# MSP430F149.net
KiCad netlist of a schematic drawn in Altium Designer
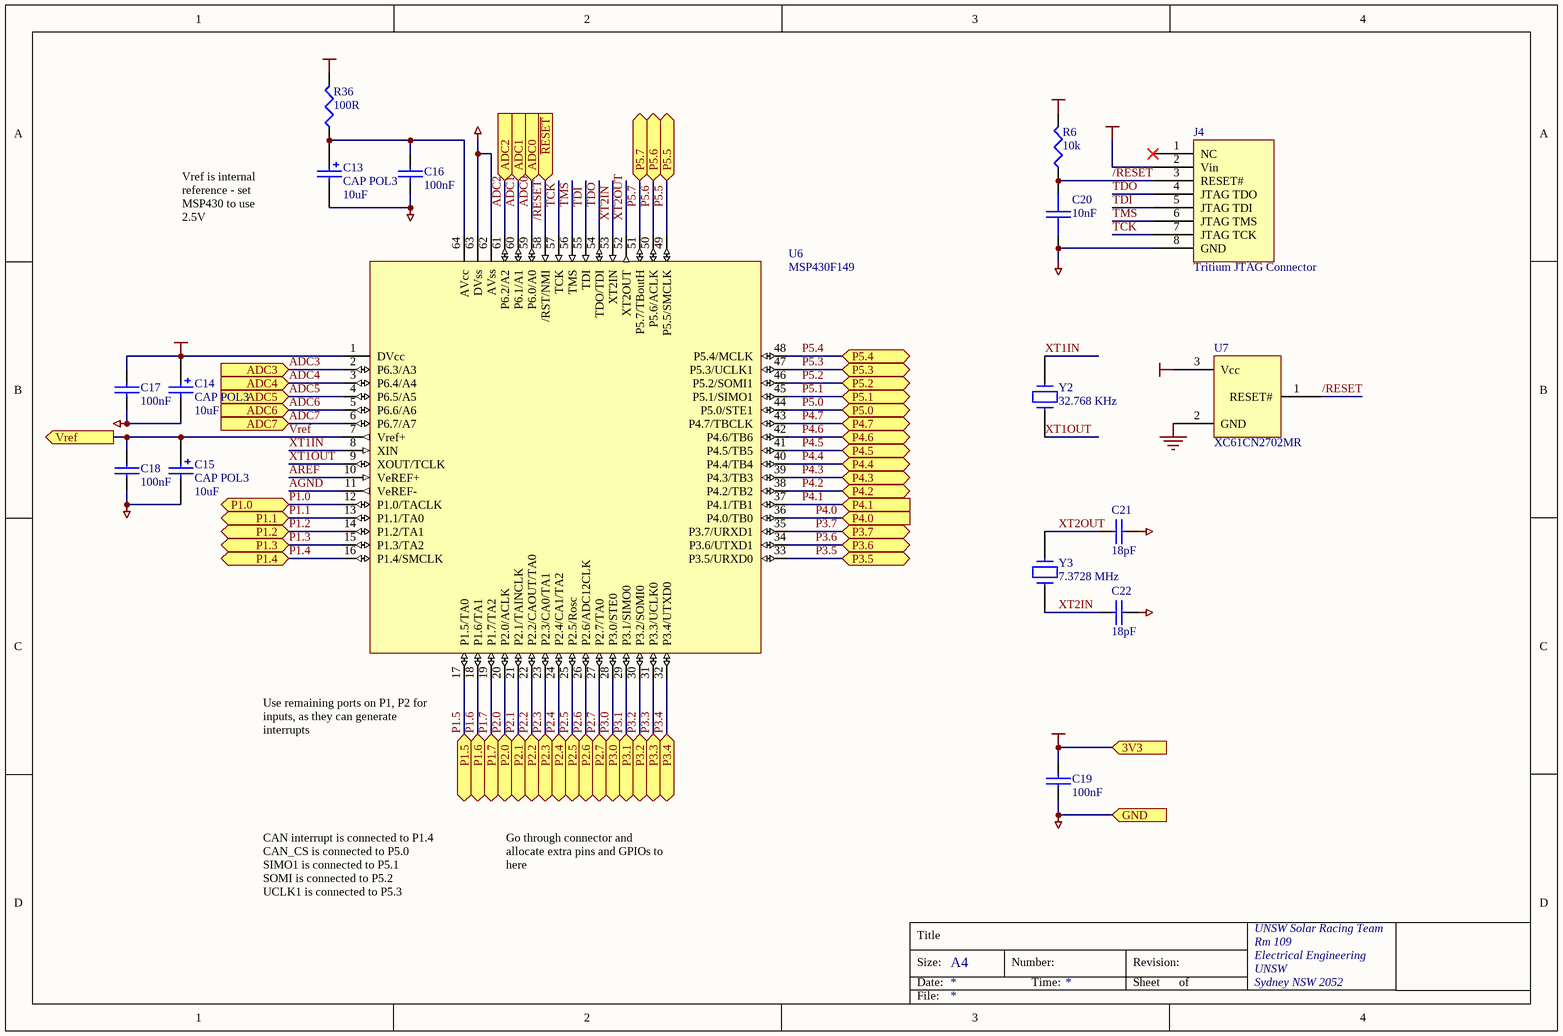
[diagram p0: MSP430F149.SCHDOC]

(export (version "E")
  (design (tool "Eeschema 10.0.6"))
  (components
    (comp (ref "C13")
      (value "CAP POL3")
      (footprint "MCCT-CASEA")
      (description "Polarized Capacitor (Surface Mount)")
      (fields
        (field (name "MANUFACTURER") "Generic Components")
        (field (name "ALTIUM_VALUE") "10uF")
        (field (name "PUBLISHER") "Altium Limited")
      )
      (libsource (lib "RCLDQ") (part "CAP POL3"))
    )
    (comp (ref "C14")
      (value "CAP POL3")
      (footprint "MCCT-CASEA")
      (description "Polarized Capacitor (Surface Mount)")
      (fields
        (field (name "MANUFACTURER") "Generic Components")
        (field (name "ALTIUM_VALUE") "10uF")
        (field (name "PUBLISHER") "Altium Limited")
      )
      (libsource (lib "RCLDQ") (part "CAP POL3"))
    )
    (comp (ref "C15")
      (value "CAP POL3")
      (footprint "MCCT-CASEA")
      (description "Polarized Capacitor (Surface Mount)")
      (fields
        (field (name "MANUFACTURER") "Generic Components")
        (field (name "ALTIUM_VALUE") "10uF")
        (field (name "PUBLISHER") "Altium Limited")
      )
      (libsource (lib "RCLDQ") (part "CAP POL3"))
    )
    (comp (ref "C16")
      (value "100nF")
      (footprint "0603")
      (description "Capacitor")
      (libsource (lib "*") (part "CAP"))
    )
    (comp (ref "C17")
      (value "100nF")
      (footprint "0603")
      (description "Capacitor")
      (libsource (lib "*") (part "CAP"))
    )
    (comp (ref "C18")
      (value "100nF")
      (footprint "0603")
      (description "Capacitor")
      (libsource (lib "*") (part "CAP"))
    )
    (comp (ref "C19")
      (value "100nF")
      (footprint "0603")
      (description "Capacitor")
      (libsource (lib "*") (part "CAP"))
    )
    (comp (ref "C20")
      (value "10nF")
      (footprint "0603")
      (description "Capacitor")
      (libsource (lib "SunswiftLib20030312RR") (part "CAP"))
    )
    (comp (ref "C21")
      (value "18pF")
      (footprint "0603")
      (description "Capacitor")
      (libsource (lib "*") (part "CAP"))
    )
    (comp (ref "C22")
      (value "18pF")
      (footprint "0603")
      (description "Capacitor")
      (libsource (lib "*") (part "CAP"))
    )
    (comp (ref "J4")
      (value "Tritium JTAG Connector")
      (footprint "HDR2X5")
      (description "Tritium JTAG interface for MSP430")
      (libsource (lib "SunswiftLib20030312RR") (part "430F_JTAG_TRITIUM"))
    )
    (comp (ref "R6")
      (value "10k")
      (footprint "0603")
      (description "Resistor")
      (libsource (lib "SunswiftLib20030312RR") (part "RES1"))
    )
    (comp (ref "R36")
      (value "100R")
      (footprint "0603")
      (description "Resistor")
      (libsource (lib "SunswiftLib20030312RR") (part "RES1"))
    )
    (comp (ref "U6")
      (value "MSP430F149")
      (footprint "QFP64")
      (libsource (lib "SunswiftLib20030312RR") (part "MSP430F14X"))
    )
    (comp (ref "U7")
      (value "XC61CN2702MR")
      (footprint "SOT23-3")
      (description "SOT23 reset generator")
      (libsource (lib "*") (part "XC61F"))
    )
    (comp (ref "Y2")
      (value "32.768 KHz")
      (footprint "WATCHA")
      (description "Crystal")
      (libsource (lib "*") (part "CRYSTAL"))
    )
    (comp (ref "Y3")
      (value "7.3728 MHz")
      (footprint "HC49/4H")
      (description "Crystal")
      (libsource (lib "*") (part "CRYSTAL"))
    )
  )
  (nets
    (net (code "1") (name "/ADC0") (class "Default")
      (node (ref "U6") (pin "59") (pinfunction "P6.0/A0_59") (pintype "bidirectional"))
    )
    (net (code "2") (name "/ADC1") (class "Default")
      (node (ref "U6") (pin "60") (pinfunction "P6.1/A1_60") (pintype "bidirectional"))
    )
    (net (code "3") (name "/ADC2") (class "Default")
      (node (ref "U6") (pin "61") (pinfunction "P6.2/A2_61") (pintype "bidirectional"))
    )
    (net (code "4") (name "/ADC3") (class "Default")
      (node (ref "U6") (pin "2") (pinfunction "P6.3/A3_2") (pintype "bidirectional"))
    )
    (net (code "5") (name "/ADC4") (class "Default")
      (node (ref "U6") (pin "3") (pinfunction "P6.4/A4_3") (pintype "bidirectional"))
    )
    (net (code "6") (name "/ADC5") (class "Default")
      (node (ref "U6") (pin "4") (pinfunction "P6.5/A5_4") (pintype "bidirectional"))
    )
    (net (code "7") (name "/ADC6") (class "Default")
      (node (ref "U6") (pin "5") (pinfunction "P6.6/A6_5") (pintype "bidirectional"))
    )
    (net (code "8") (name "/ADC7") (class "Default")
      (node (ref "U6") (pin "6") (pinfunction "P6.7/A7_6") (pintype "bidirectional"))
    )
    (net (code "9") (name "/AGND") (class "Default")
      (node (ref "U6") (pin "11") (pinfunction "VeREF-_11") (pintype "output"))
    )
    (net (code "10") (name "/AREF") (class "Default")
      (node (ref "U6") (pin "10") (pinfunction "VeREF+_10") (pintype "input"))
    )
    (net (code "11") (name "/P1.0") (class "Default")
      (node (ref "U6") (pin "12") (pinfunction "P1.0/TACLK_12") (pintype "bidirectional"))
    )
    (net (code "12") (name "/P1.1") (class "Default")
      (node (ref "U6") (pin "13") (pinfunction "P1.1/TA0_13") (pintype "bidirectional"))
    )
    (net (code "13") (name "/P1.2") (class "Default")
      (node (ref "U6") (pin "14") (pinfunction "P1.2/TA1_14") (pintype "bidirectional"))
    )
    (net (code "14") (name "/P1.3") (class "Default")
      (node (ref "U6") (pin "15") (pinfunction "P1.3/TA2_15") (pintype "bidirectional"))
    )
    (net (code "15") (name "/P1.4") (class "Default")
      (node (ref "U6") (pin "16") (pinfunction "P1.4/SMCLK_16") (pintype "bidirectional"))
    )
    (net (code "16") (name "/P1.5") (class "Default")
      (node (ref "U6") (pin "17") (pinfunction "P1.5/TA0_17") (pintype "bidirectional"))
    )
    (net (code "17") (name "/P1.6") (class "Default")
      (node (ref "U6") (pin "18") (pinfunction "P1.6/TA1_18") (pintype "bidirectional"))
    )
    (net (code "18") (name "/P1.7") (class "Default")
      (node (ref "U6") (pin "19") (pinfunction "P1.7/TA2_19") (pintype "bidirectional"))
    )
    (net (code "19") (name "/P2.0") (class "Default")
      (node (ref "U6") (pin "20") (pinfunction "P2.0/ACLK_20") (pintype "bidirectional"))
    )
    (net (code "20") (name "/P2.1") (class "Default")
      (node (ref "U6") (pin "21") (pinfunction "P2.1/TAINCLK_21") (pintype "bidirectional"))
    )
    (net (code "21") (name "/P2.2") (class "Default")
      (node (ref "U6") (pin "22") (pinfunction "P2.2/CAOUT/TA0_22") (pintype "bidirectional"))
    )
    (net (code "22") (name "/P2.3") (class "Default")
      (node (ref "U6") (pin "23") (pinfunction "P2.3/CA0/TA1_23") (pintype "bidirectional"))
    )
    (net (code "23") (name "/P2.4") (class "Default")
      (node (ref "U6") (pin "24") (pinfunction "P2.4/CA1/TA2_24") (pintype "bidirectional"))
    )
    (net (code "24") (name "/P2.5") (class "Default")
      (node (ref "U6") (pin "25") (pinfunction "P2.5/Rosc_25") (pintype "bidirectional"))
    )
    (net (code "25") (name "/P2.6") (class "Default")
      (node (ref "U6") (pin "26") (pinfunction "P2.6/ADC12CLK_26") (pintype "bidirectional"))
    )
    (net (code "26") (name "/P2.7") (class "Default")
      (node (ref "U6") (pin "27") (pinfunction "P2.7/TA0_27") (pintype "bidirectional"))
    )
    (net (code "27") (name "/P3.0") (class "Default")
      (node (ref "U6") (pin "28") (pinfunction "P3.0/STE0_28") (pintype "bidirectional"))
    )
    (net (code "28") (name "/P3.1") (class "Default")
      (node (ref "U6") (pin "29") (pinfunction "P3.1/SIMO0_29") (pintype "bidirectional"))
    )
    (net (code "29") (name "/P3.2") (class "Default")
      (node (ref "U6") (pin "30") (pinfunction "P3.2/SOMI0_30") (pintype "bidirectional"))
    )
    (net (code "30") (name "/P3.3") (class "Default")
      (node (ref "U6") (pin "31") (pinfunction "P3.3/UCLK0_31") (pintype "bidirectional"))
    )
    (net (code "31") (name "/P3.4") (class "Default")
      (node (ref "U6") (pin "32") (pinfunction "P3.4/UTXD0_32") (pintype "bidirectional"))
    )
    (net (code "32") (name "/P3.5") (class "Default")
      (node (ref "U6") (pin "33") (pinfunction "P3.5/URXD0_33") (pintype "bidirectional"))
    )
    (net (code "33") (name "/P3.6") (class "Default")
      (node (ref "U6") (pin "34") (pinfunction "P3.6/UTXD1_34") (pintype "bidirectional"))
    )
    (net (code "34") (name "/P3.7") (class "Default")
      (node (ref "U6") (pin "35") (pinfunction "P3.7/URXD1_35") (pintype "bidirectional"))
    )
    (net (code "35") (name "/P4.0") (class "Default")
      (node (ref "U6") (pin "36") (pinfunction "P4.0/TB0_36") (pintype "bidirectional"))
    )
    (net (code "36") (name "/P4.1") (class "Default")
      (node (ref "U6") (pin "37") (pinfunction "P4.1/TB1_37") (pintype "bidirectional"))
    )
    (net (code "37") (name "/P4.2") (class "Default")
      (node (ref "U6") (pin "38") (pinfunction "P4.2/TB2_38") (pintype "bidirectional"))
    )
    (net (code "38") (name "/P4.3") (class "Default")
      (node (ref "U6") (pin "39") (pinfunction "P4.3/TB3_39") (pintype "bidirectional"))
    )
    (net (code "39") (name "/P4.4") (class "Default")
      (node (ref "U6") (pin "40") (pinfunction "P4.4/TB4_40") (pintype "bidirectional"))
    )
    (net (code "40") (name "/P4.5") (class "Default")
      (node (ref "U6") (pin "41") (pinfunction "P4.5/TB5_41") (pintype "bidirectional"))
    )
    (net (code "41") (name "/P4.6") (class "Default")
      (node (ref "U6") (pin "42") (pinfunction "P4.6/TB6_42") (pintype "bidirectional"))
    )
    (net (code "42") (name "/P4.7") (class "Default")
      (node (ref "U6") (pin "43") (pinfunction "P4.7/TBCLK_43") (pintype "bidirectional"))
    )
    (net (code "43") (name "/P5.0") (class "Default")
      (node (ref "U6") (pin "44") (pinfunction "P5.0/STE1_44") (pintype "bidirectional"))
    )
    (net (code "44") (name "/P5.1") (class "Default")
      (node (ref "U6") (pin "45") (pinfunction "P5.1/SIMO1_45") (pintype "bidirectional"))
    )
    (net (code "45") (name "/P5.2") (class "Default")
      (node (ref "U6") (pin "46") (pinfunction "P5.2/SOMI1_46") (pintype "bidirectional"))
    )
    (net (code "46") (name "/P5.3") (class "Default")
      (node (ref "U6") (pin "47") (pinfunction "P5.3/UCLK1_47") (pintype "bidirectional"))
    )
    (net (code "47") (name "/P5.4") (class "Default")
      (node (ref "U6") (pin "48") (pinfunction "P5.4/MCLK_48") (pintype "bidirectional"))
    )
    (net (code "48") (name "/P5.5") (class "Default")
      (node (ref "U6") (pin "49") (pinfunction "P5.5/SMCLK_49") (pintype "bidirectional"))
    )
    (net (code "49") (name "/P5.6") (class "Default")
      (node (ref "U6") (pin "50") (pinfunction "P5.6/ACLK_50") (pintype "bidirectional"))
    )
    (net (code "50") (name "/P5.7") (class "Default")
      (node (ref "U6") (pin "51") (pinfunction "P5.7/TBoutH_51") (pintype "bidirectional"))
    )
    (net (code "51") (name "/TCK") (class "Default")
      (node (ref "J4") (pin "7") (pinfunction "JTAG_TCK_7") (pintype "passive"))
      (node (ref "U6") (pin "57") (pinfunction "TCK_57") (pintype "input"))
    )
    (net (code "52") (name "/TDI") (class "Default")
      (node (ref "J4") (pin "5") (pinfunction "JTAG_TDI_5") (pintype "passive"))
      (node (ref "U6") (pin "55") (pinfunction "TDI_55") (pintype "input"))
    )
    (net (code "53") (name "/TDO") (class "Default")
      (node (ref "J4") (pin "4") (pinfunction "JTAG_TDO_4") (pintype "passive"))
      (node (ref "U6") (pin "54") (pinfunction "TDO/TDI_54") (pintype "bidirectional"))
    )
    (net (code "54") (name "/TMS") (class "Default")
      (node (ref "J4") (pin "6") (pinfunction "JTAG_TMS_6") (pintype "passive"))
      (node (ref "U6") (pin "56") (pinfunction "TMS_56") (pintype "input"))
    )
    (net (code "55") (name "/Vref") (class "Default")
      (node (ref "C15") (pin "1") (pinfunction "1_1") (pintype "passive"))
      (node (ref "C18") (pin "1") (pinfunction "1_1") (pintype "passive"))
      (node (ref "U6") (pin "7") (pinfunction "Vref+_7") (pintype "output"))
    )
    (net (code "56") (name "/XT1IN") (class "Default")
      (node (ref "U6") (pin "8") (pinfunction "XIN_8") (pintype "input"))
      (node (ref "Y2") (pin "1") (pinfunction "1_1") (pintype "passive"))
    )
    (net (code "57") (name "/XT1OUT") (class "Default")
      (node (ref "U6") (pin "9") (pinfunction "XOUT/TCLK_9") (pintype "bidirectional"))
      (node (ref "Y2") (pin "2") (pinfunction "2_2") (pintype "passive"))
    )
    (net (code "58") (name "/XT2IN") (class "Default")
      (node (ref "C22") (pin "1") (pinfunction "1_1") (pintype "passive"))
      (node (ref "U6") (pin "53") (pinfunction "XT2IN_53") (pintype "input"))
      (node (ref "Y3") (pin "1") (pinfunction "1_1") (pintype "passive"))
    )
    (net (code "59") (name "/XT2OUT") (class "Default")
      (node (ref "C21") (pin "1") (pinfunction "1_1") (pintype "passive"))
      (node (ref "U6") (pin "52") (pinfunction "XT2OUT_52") (pintype "output"))
      (node (ref "Y3") (pin "2") (pinfunction "2_2") (pintype "passive"))
    )
    (net (code "60") (name "/{slash}RESET") (class "Default")
      (node (ref "C20") (pin "1") (pinfunction "1_1") (pintype "passive"))
      (node (ref "J4") (pin "3") (pinfunction "RESET#_3") (pintype "passive"))
      (node (ref "R6") (pin "1") (pinfunction "1_1") (pintype "passive"))
      (node (ref "U6") (pin "58") (pinfunction "/RST/NMI_58") (pintype "input"))
      (node (ref "U7") (pin "1") (pinfunction "RESET#_1") (pintype "passive"))
    )
    (net (code "61") (name "3V3") (class "Default")
      (node (ref "C14") (pin "1") (pinfunction "1_1") (pintype "passive"))
      (node (ref "C17") (pin "1") (pinfunction "1_1") (pintype "passive"))
      (node (ref "C19") (pin "1") (pinfunction "1_1") (pintype "passive"))
      (node (ref "J4") (pin "2") (pinfunction "Vin_2") (pintype "passive"))
      (node (ref "R36") (pin "2") (pinfunction "2_2") (pintype "passive"))
      (node (ref "R6") (pin "2") (pinfunction "2_2") (pintype "passive"))
      (node (ref "U6") (pin "1") (pinfunction "DVcc_1") (pintype "power_in"))
      (node (ref "U7") (pin "3") (pinfunction "Vcc_3") (pintype "passive"))
    )
    (net (code "62") (name "GND") (class "Default")
      (node (ref "C13") (pin "2") (pinfunction "2_2") (pintype "passive"))
      (node (ref "C14") (pin "2") (pinfunction "2_2") (pintype "passive"))
      (node (ref "C15") (pin "2") (pinfunction "2_2") (pintype "passive"))
      (node (ref "C16") (pin "2") (pinfunction "2_2") (pintype "passive"))
      (node (ref "C17") (pin "2") (pinfunction "2_2") (pintype "passive"))
      (node (ref "C18") (pin "2") (pinfunction "2_2") (pintype "passive"))
      (node (ref "C19") (pin "2") (pinfunction "2_2") (pintype "passive"))
      (node (ref "C20") (pin "2") (pinfunction "2_2") (pintype "passive"))
      (node (ref "C21") (pin "2") (pinfunction "2_2") (pintype "passive"))
      (node (ref "C22") (pin "2") (pinfunction "2_2") (pintype "passive"))
      (node (ref "J4") (pin "8") (pinfunction "GND_8") (pintype "passive"))
      (node (ref "U6") (pin "62") (pinfunction "AVss_62") (pintype "power_in"))
      (node (ref "U6") (pin "63") (pinfunction "DVss_63") (pintype "power_in"))
      (node (ref "U7") (pin "2") (pinfunction "GND_2") (pintype "passive"))
    )
    (net (code "63") (name "Net-(U6-AVcc)") (class "Default")
      (node (ref "C13") (pin "1") (pinfunction "1_1") (pintype "passive"))
      (node (ref "C16") (pin "1") (pinfunction "1_1") (pintype "passive"))
      (node (ref "R36") (pin "1") (pinfunction "1_1") (pintype "passive"))
      (node (ref "U6") (pin "64") (pinfunction "AVcc_64") (pintype "power_in"))
    )
    (net (code "64") (name "unconnected-(J4-NC-Pad1)") (class "Default")
      (node (ref "J4") (pin "1") (pinfunction "NC_1") (pintype "passive+no_connect"))
    )
  )
)
